# PowerDongle.net
KiCad netlist of a schematic drawn in EAGLE
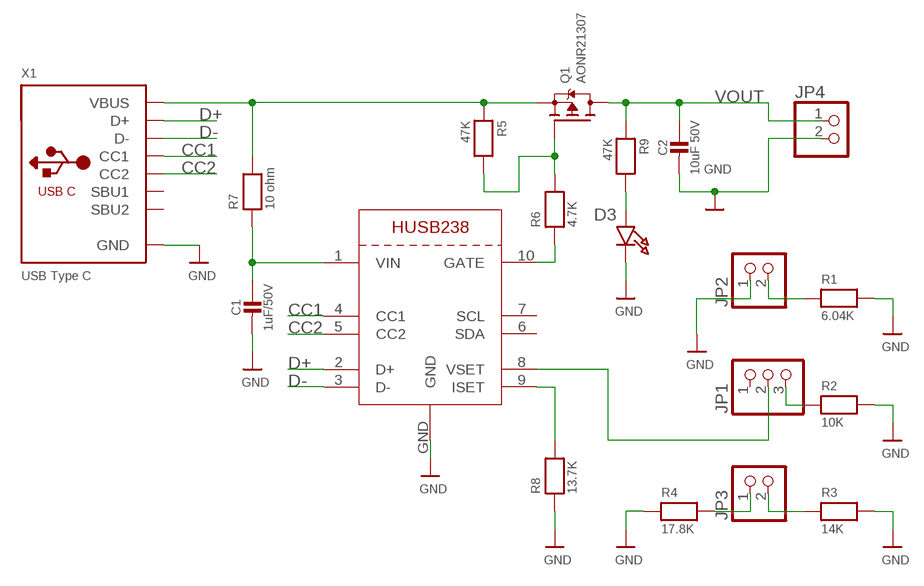
[diagram p0: schematic, sheet 1]

(export (version "E")
  (design (tool "Eeschema 10.0.6"))
  (components
    (comp (ref "C1")
      (value "1uF/50V")
      (footprint "eagle-import:_0805MP")
      (libsource (lib "eagle-import") (part "CAP_CERAMIC_0805MP"))
    )
    (comp (ref "C2")
      (value "10uF 50V")
      (footprint "eagle-import:_0805MP")
      (libsource (lib "eagle-import") (part "CAP_CERAMIC_0805MP"))
    )
    (comp (ref "D3")
      (value "Green")
      (footprint "eagle-import:CHIPLED_0805_NOOUTLINE")
      (libsource (lib "eagle-import") (part "LED0805_NOOUTLINE"))
    )
    (comp (ref "JP1")
      (value "HEADER-1X3ROUND")
      (footprint "eagle-import:1X03_ROUND")
      (libsource (lib "eagle-import") (part "HEADER-1X3ROUND"))
    )
    (comp (ref "JP2")
      (value "HEADER-1X2ROUND")
      (footprint "eagle-import:1X02_ROUND")
      (libsource (lib "eagle-import") (part "HEADER-1X2ROUND"))
    )
    (comp (ref "JP3")
      (value "HEADER-1X2ROUND")
      (footprint "eagle-import:1X02_ROUND")
      (libsource (lib "eagle-import") (part "HEADER-1X2ROUND"))
    )
    (comp (ref "JP4")
      (value "HEADER-1X2ROUND")
      (footprint "eagle-import:1X02_ROUND")
      (libsource (lib "eagle-import") (part "HEADER-1X2ROUND"))
    )
    (comp (ref "Q1")
      (value "AONR21307")
      (footprint "eagle-import:POWERDI3333")
      (libsource (lib "eagle-import") (part "MOSFET-P-POWERDI3333"))
    )
    (comp (ref "R1")
      (value "6.04K")
      (footprint "eagle-import:_0805MP")
      (libsource (lib "eagle-import") (part "RESISTOR_0805MP"))
    )
    (comp (ref "R2")
      (value "10K")
      (footprint "eagle-import:_0805MP")
      (libsource (lib "eagle-import") (part "RESISTOR_0805MP"))
    )
    (comp (ref "R3")
      (value "14K")
      (footprint "eagle-import:_0805MP")
      (libsource (lib "eagle-import") (part "RESISTOR_0805MP"))
    )
    (comp (ref "R4")
      (value "17.8K")
      (footprint "eagle-import:_0805MP")
      (libsource (lib "eagle-import") (part "RESISTOR_0805MP"))
    )
    (comp (ref "R5")
      (value "47K")
      (footprint "eagle-import:_0805MP")
      (libsource (lib "eagle-import") (part "RESISTOR_0805MP"))
    )
    (comp (ref "R6")
      (value "4.7K")
      (footprint "eagle-import:_0805MP")
      (libsource (lib "eagle-import") (part "RESISTOR_0805MP"))
    )
    (comp (ref "R7")
      (value "10 ohm")
      (footprint "eagle-import:_0805MP")
      (libsource (lib "eagle-import") (part "RESISTOR_0805MP"))
    )
    (comp (ref "R8")
      (value "13.7K")
      (footprint "eagle-import:_0805MP")
      (libsource (lib "eagle-import") (part "RESISTOR_0805MP"))
    )
    (comp (ref "R9")
      (value "47K")
      (footprint "eagle-import:_0805MP")
      (libsource (lib "eagle-import") (part "RESISTOR_0805MP"))
    )
    (comp (ref "X1")
      (value "USB Type C")
      (footprint "eagle-import:USB_C_CUSB31-CFM2AX-01-X")
      (libsource (lib "eagle-import") (part "USB_C"))
    )
    (comp (ref "X3")
      (value "HUSB238")
      (footprint "eagle-import:DFN10_3X3MM")
      (libsource (lib "eagle-import") (part "HUSB238"))
    )
  )
  (nets
    (net (code "1") (name "/CC1") (class "Default")
      (node (ref "X1") (pin "A5") (pinfunction "CC1_A5") (pintype "bidirectional"))
      (node (ref "X3") (pin "4") (pinfunction "CC1_4") (pintype "input"))
    )
    (net (code "2") (name "/CC2") (class "Default")
      (node (ref "X1") (pin "B5") (pinfunction "CC2_B5") (pintype "bidirectional"))
      (node (ref "X3") (pin "5") (pinfunction "CC2_5") (pintype "input"))
    )
    (net (code "3") (name "/D+") (class "Default")
      (node (ref "X1") (pin "A6") (pinfunction "D+_A6") (pintype "bidirectional"))
      (node (ref "X1") (pin "B6") (pinfunction "D+_B6") (pintype "bidirectional"))
      (node (ref "X3") (pin "2") (pinfunction "D+_2") (pintype "input"))
    )
    (net (code "4") (name "/D-") (class "Default")
      (node (ref "X1") (pin "A7") (pinfunction "D-_A7") (pintype "bidirectional"))
      (node (ref "X1") (pin "B7") (pinfunction "D-_B7") (pintype "bidirectional"))
      (node (ref "X3") (pin "3") (pinfunction "D-_3") (pintype "input"))
    )
    (net (code "5") (name "/VOUT") (class "Default")
      (node (ref "C2") (pin "1") (pinfunction "P$1_1") (pintype "passive"))
      (node (ref "JP4") (pin "1") (pinfunction "1_1") (pintype "passive"))
      (node (ref "Q1") (pin "5678") (pinfunction "D_5678") (pintype "passive"))
      (node (ref "R9") (pin "1") (pinfunction "1_1") (pintype "passive"))
    )
    (net (code "6") (name "GND") (class "Default")
      (node (ref "C1") (pin "2") (pinfunction "P$2_2") (pintype "passive"))
      (node (ref "C2") (pin "2") (pinfunction "P$2_2") (pintype "passive"))
      (node (ref "D3") (pin "C") (pinfunction "C_C") (pintype "passive"))
      (node (ref "JP2") (pin "1") (pinfunction "1_1") (pintype "passive"))
      (node (ref "JP4") (pin "2") (pinfunction "2_2") (pintype "passive"))
      (node (ref "R1") (pin "2") (pinfunction "2_2") (pintype "passive"))
      (node (ref "R2") (pin "2") (pinfunction "2_2") (pintype "passive"))
      (node (ref "R3") (pin "2") (pinfunction "2_2") (pintype "passive"))
      (node (ref "R4") (pin "1") (pinfunction "1_1") (pintype "passive"))
      (node (ref "R8") (pin "1") (pinfunction "1_1") (pintype "passive"))
      (node (ref "X1") (pin "A1B12") (pinfunction "GND_A1B12") (pintype "power_in"))
      (node (ref "X1") (pin "B1A12") (pinfunction "GND_B1A12") (pintype "power_in"))
      (node (ref "X3") (pin "GND") (pinfunction "GND_GND") (pintype "power_in"))
    )
    (net (code "7") (name "Net-(C1-P$1)") (class "Default")
      (node (ref "C1") (pin "1") (pinfunction "P$1_1") (pintype "passive"))
      (node (ref "R7") (pin "1") (pinfunction "1_1") (pintype "passive"))
      (node (ref "X3") (pin "1") (pinfunction "VIN_1") (pintype "power_in"))
    )
    (net (code "8") (name "Net-(D3-PadA)") (class "Default")
      (node (ref "D3") (pin "A") (pinfunction "A_A") (pintype "passive"))
      (node (ref "R9") (pin "2") (pinfunction "2_2") (pintype "passive"))
    )
    (net (code "9") (name "Net-(JP1-Pad3)") (class "Default")
      (node (ref "JP1") (pin "3") (pinfunction "3_3") (pintype "passive"))
      (node (ref "R2") (pin "1") (pinfunction "1_1") (pintype "passive"))
    )
    (net (code "10") (name "Net-(JP2-Pad2)") (class "Default")
      (node (ref "JP2") (pin "2") (pinfunction "2_2") (pintype "passive"))
      (node (ref "R1") (pin "1") (pinfunction "1_1") (pintype "passive"))
    )
    (net (code "11") (name "Net-(JP3-Pad1)") (class "Default")
      (node (ref "JP3") (pin "1") (pinfunction "1_1") (pintype "passive"))
      (node (ref "R4") (pin "2") (pinfunction "2_2") (pintype "passive"))
    )
    (net (code "12") (name "Net-(JP3-Pad2)") (class "Default")
      (node (ref "JP3") (pin "2") (pinfunction "2_2") (pintype "passive"))
      (node (ref "R3") (pin "1") (pinfunction "1_1") (pintype "passive"))
    )
    (net (code "13") (name "Net-(Q1-G)") (class "Default")
      (node (ref "Q1") (pin "4") (pinfunction "G_4") (pintype "passive"))
      (node (ref "R5") (pin "2") (pinfunction "2_2") (pintype "passive"))
      (node (ref "R6") (pin "2") (pinfunction "2_2") (pintype "passive"))
    )
    (net (code "14") (name "Net-(Q1-S-Pad1)") (class "Default")
      (node (ref "Q1") (pin "1") (pinfunction "S_1") (pintype "passive"))
      (node (ref "Q1") (pin "2") (pinfunction "S_2") (pintype "passive"))
      (node (ref "Q1") (pin "3") (pinfunction "S_3") (pintype "passive"))
      (node (ref "R5") (pin "1") (pinfunction "1_1") (pintype "passive"))
      (node (ref "R7") (pin "2") (pinfunction "2_2") (pintype "passive"))
      (node (ref "X1") (pin "A4B9") (pinfunction "VBUS_A4B9") (pintype "power_in"))
      (node (ref "X1") (pin "B4A9") (pinfunction "VBUS_B4A9") (pintype "power_in"))
    )
    (net (code "15") (name "Net-(X3-GATE)") (class "Default")
      (node (ref "R6") (pin "1") (pinfunction "1_1") (pintype "passive"))
      (node (ref "X3") (pin "10") (pinfunction "GATE_10") (pintype "output"))
    )
    (net (code "16") (name "Net-(X3-ISET)") (class "Default")
      (node (ref "R8") (pin "2") (pinfunction "2_2") (pintype "passive"))
      (node (ref "X3") (pin "9") (pinfunction "ISET_9") (pintype "passive"))
    )
    (net (code "17") (name "Net-(X3-VSET)") (class "Default")
      (node (ref "JP1") (pin "2") (pinfunction "2_2") (pintype "passive"))
      (node (ref "X3") (pin "8") (pinfunction "VSET_8") (pintype "passive"))
    )
    (net (code "18") (name "unconnected-(JP1-Pad1)") (class "Default")
      (node (ref "JP1") (pin "1") (pinfunction "1_1") (pintype "passive"))
    )
    (net (code "19") (name "unconnected-(X1-SBU1-PadA8)") (class "Default")
      (node (ref "X1") (pin "A8") (pinfunction "SBU1_A8") (pintype "bidirectional"))
    )
    (net (code "20") (name "unconnected-(X1-SBU2-PadB8)") (class "Default")
      (node (ref "X1") (pin "B8") (pinfunction "SBU2_B8") (pintype "bidirectional"))
    )
    (net (code "21") (name "unconnected-(X3-SCL-Pad7)") (class "Default")
      (node (ref "X3") (pin "7") (pinfunction "SCL_7") (pintype "bidirectional"))
    )
    (net (code "22") (name "unconnected-(X3-SDA-Pad6)") (class "Default")
      (node (ref "X3") (pin "6") (pinfunction "SDA_6") (pintype "bidirectional"))
    )
  )
)
